# Franzino.net
KiCad netlist of a schematic drawn in EAGLE
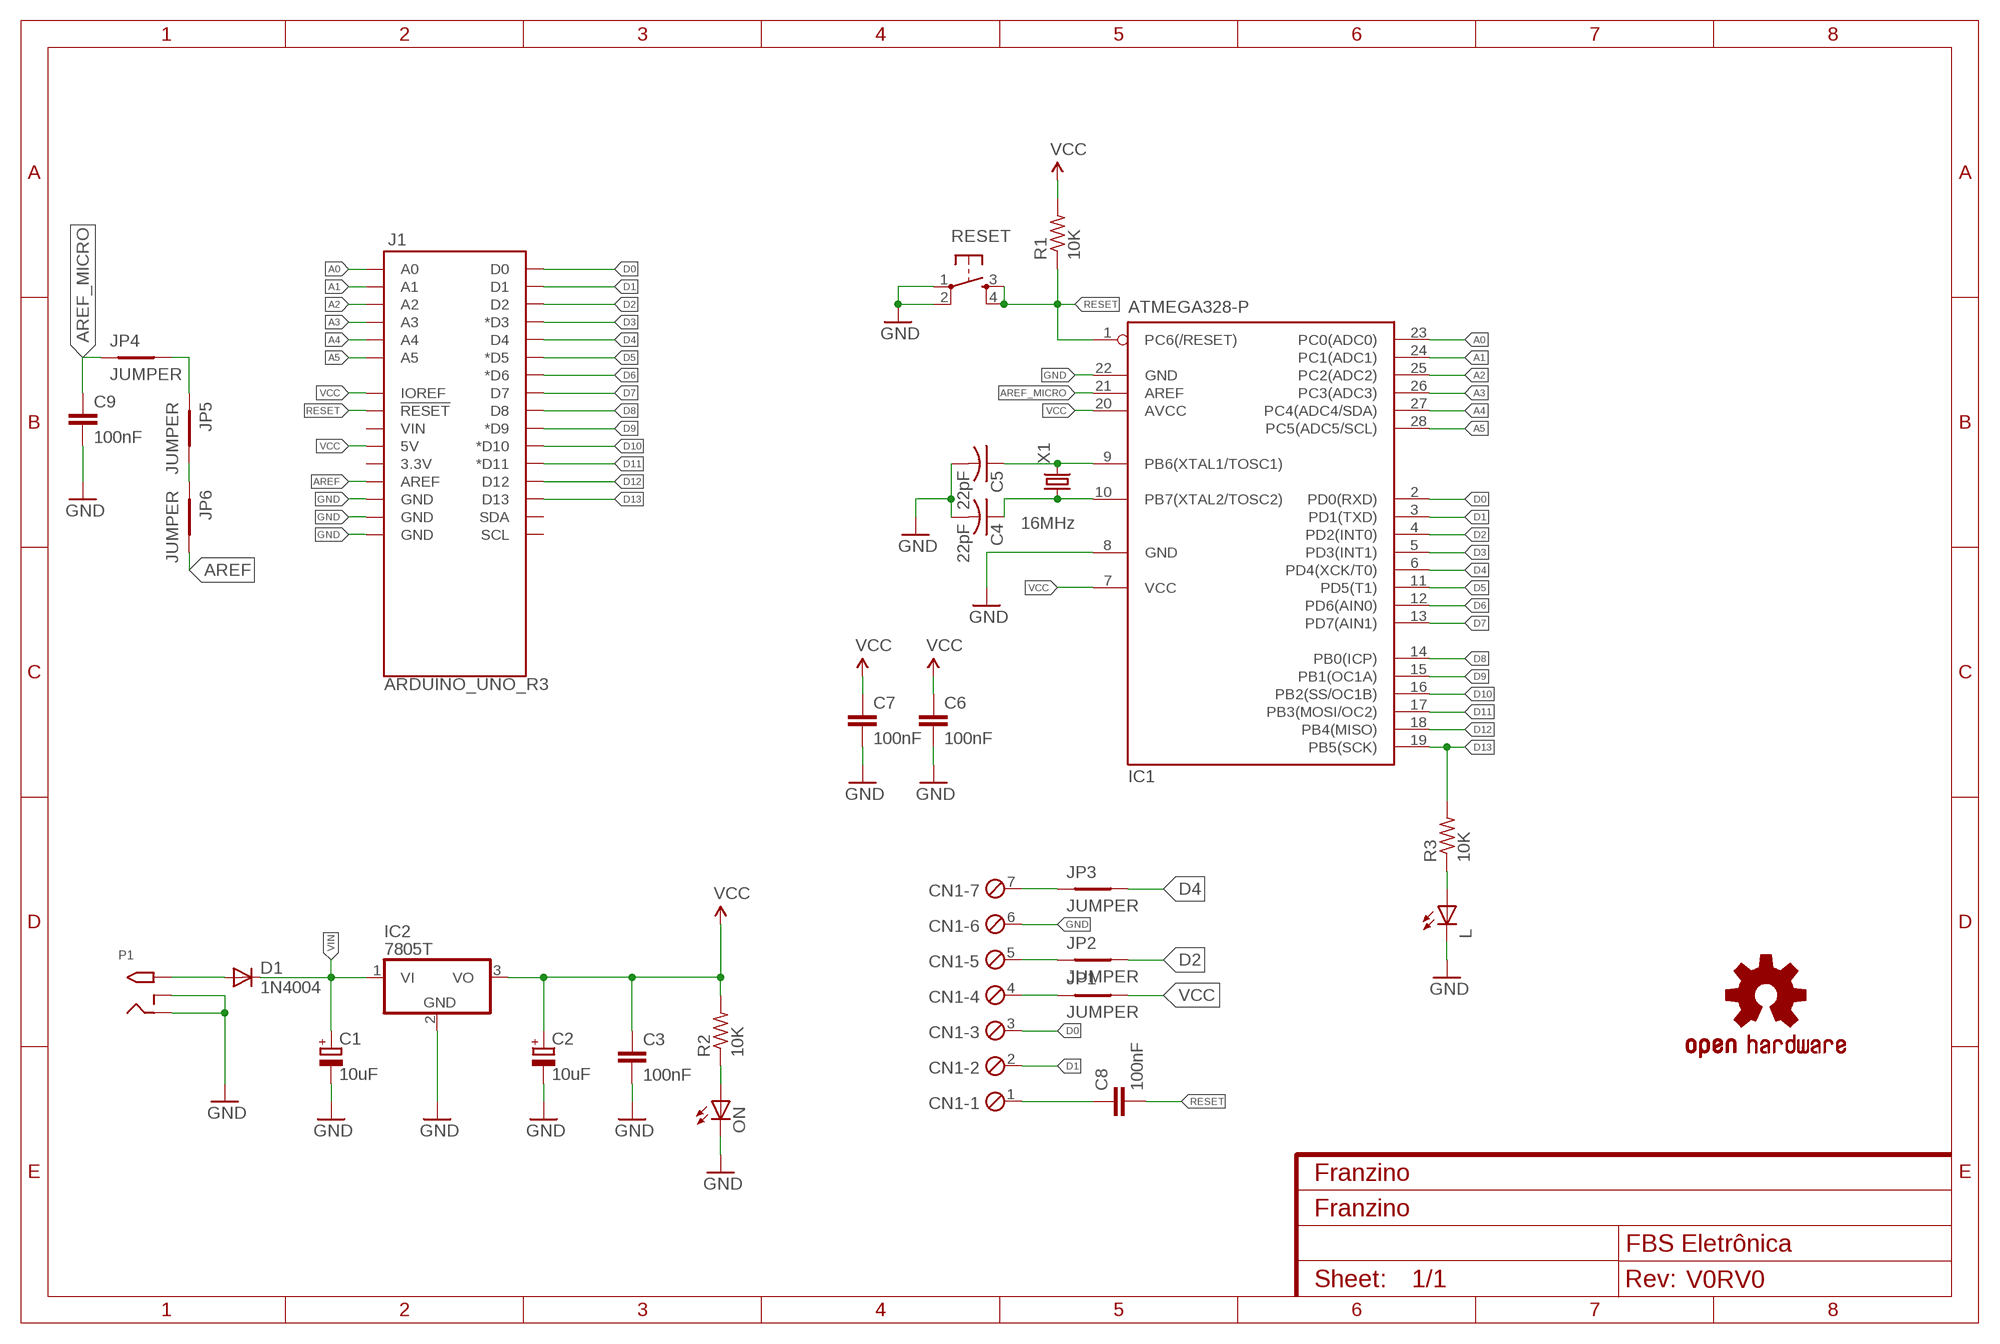
[diagram p0: schematic, sheet 1]

(export (version "E")
  (design (tool "Eeschema 10.0.6"))
  (components
    (comp (ref "C1")
      (value "10uF")
      (footprint "eagle-import:E2,5-6")
      (libsource (lib "eagle-import") (part "CPOL-EUE2.5-6"))
    )
    (comp (ref "C2")
      (value "10uF")
      (footprint "eagle-import:E2,5-6")
      (libsource (lib "eagle-import") (part "CPOL-EUE2.5-6"))
    )
    (comp (ref "C3")
      (value "100nF")
      (footprint "eagle-import:C0805K")
      (libsource (lib "eagle-import") (part "C-EUC0805K"))
    )
    (comp (ref "C4")
      (value "22pF")
      (footprint "eagle-import:C025-024X044")
      (libsource (lib "eagle-import") (part "C-US025-024X044"))
    )
    (comp (ref "C5")
      (value "22pF")
      (footprint "eagle-import:C025-024X044")
      (libsource (lib "eagle-import") (part "C-US025-024X044"))
    )
    (comp (ref "C6")
      (value "100nF")
      (footprint "eagle-import:C0805K")
      (libsource (lib "eagle-import") (part "resistor_C-EUC0805K"))
    )
    (comp (ref "C7")
      (value "100nF")
      (footprint "eagle-import:C0805K")
      (libsource (lib "eagle-import") (part "resistor_C-EUC0805K"))
    )
    (comp (ref "C8")
      (value "100nF")
      (footprint "eagle-import:C0805K")
      (libsource (lib "eagle-import") (part "resistor_C-EUC0805K"))
    )
    (comp (ref "C9")
      (value "100nF")
      (footprint "eagle-import:C0805K")
      (libsource (lib "eagle-import") (part "resistor_C-EUC0805K"))
    )
    (comp (ref "CN1")
      (value "BARRA de PINOS 6 VIAS")
      (footprint "eagle-import:7POL254")
      (libsource (lib "eagle-import") (part "MPT7"))
    )
    (comp (ref "D1")
      (value "1N4004")
      (footprint "eagle-import:DO41-10")
      (libsource (lib "eagle-import") (part "1N4004"))
    )
    (comp (ref "IC1")
      (value "ATMEGA328-P")
      (footprint "eagle-import:DIL28-3")
      (libsource (lib "eagle-import") (part "MEGA8-P"))
    )
    (comp (ref "IC2")
      (value "7805T")
      (footprint "eagle-import:TO220H")
      (libsource (lib "eagle-import") (part "78T05"))
    )
    (comp (ref "J1")
      (value "ARDUINO_UNO_R3")
      (footprint "eagle-import:ARDUINO_UNO_R3_PINS")
      (libsource (lib "eagle-import") (part "ARDUINO_UNO_R3"))
    )
    (comp (ref "JP1")
      (value "JUMPER")
      (footprint "eagle-import:JUMP10")
      (libsource (lib "eagle-import") (part "JUMPER"))
    )
    (comp (ref "JP2")
      (value "JUMPER")
      (footprint "eagle-import:JUMP10")
      (libsource (lib "eagle-import") (part "JUMPER"))
    )
    (comp (ref "JP3")
      (value "JUMPER")
      (footprint "eagle-import:JUMP10")
      (libsource (lib "eagle-import") (part "JUMPER"))
    )
    (comp (ref "JP4")
      (value "JUMPER")
      (footprint "eagle-import:JUMP10")
      (libsource (lib "eagle-import") (part "JUMPER"))
    )
    (comp (ref "JP5")
      (value "JUMPER")
      (footprint "eagle-import:JUMP10")
      (libsource (lib "eagle-import") (part "JUMPER"))
    )
    (comp (ref "JP6")
      (value "JUMPER")
      (footprint "eagle-import:JUMP10")
      (libsource (lib "eagle-import") (part "JUMPER"))
    )
    (comp (ref "L")
      (value "LED 3mm Amarelo")
      (footprint "eagle-import:LED3MM")
      (libsource (lib "eagle-import") (part "LED3MM"))
    )
    (comp (ref "LOGO2")
      (value "OSHW-LOGOL")
      (footprint "eagle-import:OSHW-LOGO-L")
      (libsource (lib "eagle-import") (part "OSHW-LOGOL"))
    )
    (comp (ref "ON")
      (value "LED 3 mm VERDE")
      (footprint "eagle-import:LED3MM")
      (libsource (lib "eagle-import") (part "LED3MM"))
    )
    (comp (ref "P1")
      (value "2.1MMJACKTHM")
      (footprint "eagle-import:PJ-102A")
      (libsource (lib "eagle-import") (part "2.1MMJACKTHM"))
    )
    (comp (ref "R1")
      (value "10K")
      (footprint "eagle-import:0207_10")
      (libsource (lib "eagle-import") (part "R-US_0207/10"))
    )
    (comp (ref "R2")
      (value "10K")
      (footprint "eagle-import:0207_10")
      (libsource (lib "eagle-import") (part "R-US_0207/10"))
    )
    (comp (ref "R3")
      (value "10K")
      (footprint "eagle-import:0207_10")
      (libsource (lib "eagle-import") (part "R-US_0207/10"))
    )
    (comp (ref "RESET")
      (value "CHAVE TACTIL 6 mm")
      (footprint "eagle-import:TACTILE-PTH")
      (libsource (lib "eagle-import") (part "TAC_SWITCHPTH"))
    )
    (comp (ref "X1")
      (value "16MHz")
      (footprint "eagle-import:HC49_S")
      (libsource (lib "eagle-import") (part "CRYSTALHC49S"))
    )
  )
  (nets
    (net (code "1") (name "A0") (class "Default")
      (node (ref "IC1") (pin "23") (pinfunction "PC0(ADC0)_23") (pintype "bidirectional"))
      (node (ref "J1") (pin "A0") (pinfunction "A0_A0") (pintype "bidirectional"))
    )
    (net (code "2") (name "A1") (class "Default")
      (node (ref "IC1") (pin "24") (pinfunction "PC1(ADC1)_24") (pintype "bidirectional"))
      (node (ref "J1") (pin "A1") (pinfunction "A1_A1") (pintype "bidirectional"))
    )
    (net (code "3") (name "A2") (class "Default")
      (node (ref "IC1") (pin "25") (pinfunction "PC2(ADC2)_25") (pintype "bidirectional"))
      (node (ref "J1") (pin "A2") (pinfunction "A2_A2") (pintype "bidirectional"))
    )
    (net (code "4") (name "A3") (class "Default")
      (node (ref "IC1") (pin "26") (pinfunction "PC3(ADC3)_26") (pintype "bidirectional"))
      (node (ref "J1") (pin "A3") (pinfunction "A3_A3") (pintype "bidirectional"))
    )
    (net (code "5") (name "A4") (class "Default")
      (node (ref "IC1") (pin "27") (pinfunction "PC4(ADC4/SDA)_27") (pintype "bidirectional"))
      (node (ref "J1") (pin "A4") (pinfunction "A4_A4") (pintype "bidirectional"))
    )
    (net (code "6") (name "A5") (class "Default")
      (node (ref "IC1") (pin "28") (pinfunction "PC5(ADC5/SCL)_28") (pintype "bidirectional"))
      (node (ref "J1") (pin "A5") (pinfunction "A5_A5") (pintype "bidirectional"))
    )
    (net (code "7") (name "AREF") (class "Default")
      (node (ref "J1") (pin "AREF") (pinfunction "AREF_AREF") (pintype "bidirectional"))
      (node (ref "JP6") (pin "2") (pinfunction "2_2") (pintype "passive"))
    )
    (net (code "8") (name "AREF_MICRO") (class "Default")
      (node (ref "C9") (pin "1") (pinfunction "1_1") (pintype "passive"))
      (node (ref "IC1") (pin "21") (pinfunction "AREF_21") (pintype "passive"))
      (node (ref "JP4") (pin "1") (pinfunction "1_1") (pintype "passive"))
    )
    (net (code "9") (name "D0") (class "Default")
      (node (ref "CN1") (pin "3") (pinfunction "1_3") (pintype "passive"))
      (node (ref "IC1") (pin "2") (pinfunction "PD0(RXD)_2") (pintype "bidirectional"))
      (node (ref "J1") (pin "D0") (pinfunction "D0_D0") (pintype "bidirectional"))
    )
    (net (code "10") (name "D1") (class "Default")
      (node (ref "CN1") (pin "2") (pinfunction "1_2") (pintype "passive"))
      (node (ref "IC1") (pin "3") (pinfunction "PD1(TXD)_3") (pintype "bidirectional"))
      (node (ref "J1") (pin "D1") (pinfunction "D1_D1") (pintype "bidirectional"))
    )
    (net (code "11") (name "D2") (class "Default")
      (node (ref "IC1") (pin "4") (pinfunction "PD2(INT0)_4") (pintype "bidirectional"))
      (node (ref "J1") (pin "D2") (pinfunction "D2_D2") (pintype "bidirectional"))
      (node (ref "JP2") (pin "2") (pinfunction "2_2") (pintype "passive"))
    )
    (net (code "12") (name "D3") (class "Default")
      (node (ref "IC1") (pin "5") (pinfunction "PD3(INT1)_5") (pintype "bidirectional"))
      (node (ref "J1") (pin "D3") (pinfunction "*D3_D3") (pintype "bidirectional"))
    )
    (net (code "13") (name "D4") (class "Default")
      (node (ref "IC1") (pin "6") (pinfunction "PD4(XCK/T0)_6") (pintype "bidirectional"))
      (node (ref "J1") (pin "D4") (pinfunction "D4_D4") (pintype "bidirectional"))
      (node (ref "JP3") (pin "2") (pinfunction "2_2") (pintype "passive"))
    )
    (net (code "14") (name "D5") (class "Default")
      (node (ref "IC1") (pin "11") (pinfunction "PD5(T1)_11") (pintype "bidirectional"))
      (node (ref "J1") (pin "D5") (pinfunction "*D5_D5") (pintype "bidirectional"))
    )
    (net (code "15") (name "D6") (class "Default")
      (node (ref "IC1") (pin "12") (pinfunction "PD6(AIN0)_12") (pintype "bidirectional"))
      (node (ref "J1") (pin "D6") (pinfunction "*D6_D6") (pintype "bidirectional"))
    )
    (net (code "16") (name "D7") (class "Default")
      (node (ref "IC1") (pin "13") (pinfunction "PD7(AIN1)_13") (pintype "bidirectional"))
      (node (ref "J1") (pin "D7") (pinfunction "D7_D7") (pintype "bidirectional"))
    )
    (net (code "17") (name "D8") (class "Default")
      (node (ref "IC1") (pin "14") (pinfunction "PB0(ICP)_14") (pintype "bidirectional"))
      (node (ref "J1") (pin "D8") (pinfunction "D8_D8") (pintype "bidirectional"))
    )
    (net (code "18") (name "D9") (class "Default")
      (node (ref "IC1") (pin "15") (pinfunction "PB1(OC1A)_15") (pintype "bidirectional"))
      (node (ref "J1") (pin "D9") (pinfunction "*D9_D9") (pintype "bidirectional"))
    )
    (net (code "19") (name "D10") (class "Default")
      (node (ref "IC1") (pin "16") (pinfunction "PB2(SS/OC1B)_16") (pintype "bidirectional"))
      (node (ref "J1") (pin "D10") (pinfunction "*D10_D10") (pintype "bidirectional"))
    )
    (net (code "20") (name "D11") (class "Default")
      (node (ref "IC1") (pin "17") (pinfunction "PB3(MOSI/OC2)_17") (pintype "bidirectional"))
      (node (ref "J1") (pin "D11") (pinfunction "*D11_D11") (pintype "bidirectional"))
    )
    (net (code "21") (name "D12") (class "Default")
      (node (ref "IC1") (pin "18") (pinfunction "PB4(MISO)_18") (pintype "bidirectional"))
      (node (ref "J1") (pin "D12") (pinfunction "D12_D12") (pintype "bidirectional"))
    )
    (net (code "22") (name "D13") (class "Default")
      (node (ref "IC1") (pin "19") (pinfunction "PB5(SCK)_19") (pintype "bidirectional"))
      (node (ref "J1") (pin "D13") (pinfunction "D13_D13") (pintype "bidirectional"))
      (node (ref "R3") (pin "2") (pinfunction "2_2") (pintype "passive"))
    )
    (net (code "23") (name "GND") (class "Default")
      (node (ref "C1") (pin "-") (pinfunction "-_-") (pintype "passive"))
      (node (ref "C2") (pin "-") (pinfunction "-_-") (pintype "passive"))
      (node (ref "C3") (pin "2") (pinfunction "2_2") (pintype "passive"))
      (node (ref "C4") (pin "2") (pinfunction "2_2") (pintype "passive"))
      (node (ref "C5") (pin "2") (pinfunction "2_2") (pintype "passive"))
      (node (ref "C6") (pin "2") (pinfunction "2_2") (pintype "passive"))
      (node (ref "C7") (pin "2") (pinfunction "2_2") (pintype "passive"))
      (node (ref "C9") (pin "2") (pinfunction "2_2") (pintype "passive"))
      (node (ref "CN1") (pin "6") (pinfunction "1_6") (pintype "passive"))
      (node (ref "IC1") (pin "22") (pinfunction "GND_22") (pintype "power_in"))
      (node (ref "IC1") (pin "8") (pinfunction "GND_8") (pintype "power_in"))
      (node (ref "IC2") (pin "2") (pinfunction "GND_2") (pintype "passive"))
      (node (ref "J1") (pin "GND@1") (pinfunction "GND_GND@1") (pintype "bidirectional"))
      (node (ref "J1") (pin "GND@2") (pinfunction "GND_GND@2") (pintype "bidirectional"))
      (node (ref "J1") (pin "GND@3") (pinfunction "GND_GND@3") (pintype "bidirectional"))
      (node (ref "L") (pin "K") (pinfunction "C_K") (pintype "passive"))
      (node (ref "ON") (pin "K") (pinfunction "C_K") (pintype "passive"))
      (node (ref "P1") (pin "RING") (pinfunction "RING_RING") (pintype "bidirectional"))
      (node (ref "P1") (pin "RING_SW") (pinfunction "RING_SW_RING_SW") (pintype "bidirectional"))
      (node (ref "RESET") (pin "1") (pinfunction "1_1") (pintype "passive"))
      (node (ref "RESET") (pin "2") (pinfunction "2_2") (pintype "passive"))
    )
    (net (code "24") (name "Net-(C8-Pad1)") (class "Default")
      (node (ref "C8") (pin "1") (pinfunction "1_1") (pintype "passive"))
      (node (ref "CN1") (pin "1") (pinfunction "1_1") (pintype "passive"))
    )
    (net (code "25") (name "Net-(CN1D-1)") (class "Default")
      (node (ref "CN1") (pin "4") (pinfunction "1_4") (pintype "passive"))
      (node (ref "JP1") (pin "1") (pinfunction "1_1") (pintype "passive"))
    )
    (net (code "26") (name "Net-(CN1E-1)") (class "Default")
      (node (ref "CN1") (pin "5") (pinfunction "1_5") (pintype "passive"))
      (node (ref "JP2") (pin "1") (pinfunction "1_1") (pintype "passive"))
    )
    (net (code "27") (name "Net-(CN1G-1)") (class "Default")
      (node (ref "CN1") (pin "7") (pinfunction "1_7") (pintype "passive"))
      (node (ref "JP3") (pin "1") (pinfunction "1_1") (pintype "passive"))
    )
    (net (code "28") (name "Net-(D1-PadA)") (class "Default")
      (node (ref "D1") (pin "A") (pinfunction "A_A") (pintype "passive"))
      (node (ref "P1") (pin "TIP") (pinfunction "TIP_TIP") (pintype "bidirectional"))
    )
    (net (code "29") (name "Net-(IC1-PB6(XTAL1{slash}TOSC1))") (class "Default")
      (node (ref "C5") (pin "1") (pinfunction "1_1") (pintype "passive"))
      (node (ref "IC1") (pin "9") (pinfunction "PB6(XTAL1/TOSC1)_9") (pintype "bidirectional"))
      (node (ref "X1") (pin "2") (pinfunction "2_2") (pintype "passive"))
    )
    (net (code "30") (name "Net-(IC1-PB7(XTAL2{slash}TOSC2))") (class "Default")
      (node (ref "C4") (pin "1") (pinfunction "1_1") (pintype "passive"))
      (node (ref "IC1") (pin "10") (pinfunction "PB7(XTAL2/TOSC2)_10") (pintype "bidirectional"))
      (node (ref "X1") (pin "1") (pinfunction "1_1") (pintype "passive"))
    )
    (net (code "31") (name "Net-(JP4-Pad2)") (class "Default")
      (node (ref "JP4") (pin "2") (pinfunction "2_2") (pintype "passive"))
      (node (ref "JP5") (pin "1") (pinfunction "1_1") (pintype "passive"))
    )
    (net (code "32") (name "Net-(JP5-Pad2)") (class "Default")
      (node (ref "JP5") (pin "2") (pinfunction "2_2") (pintype "passive"))
      (node (ref "JP6") (pin "1") (pinfunction "1_1") (pintype "passive"))
    )
    (net (code "33") (name "Net-(L-PadA)") (class "Default")
      (node (ref "L") (pin "A") (pinfunction "A_A") (pintype "passive"))
      (node (ref "R3") (pin "1") (pinfunction "1_1") (pintype "passive"))
    )
    (net (code "34") (name "Net-(ON-PadA)") (class "Default")
      (node (ref "ON") (pin "A") (pinfunction "A_A") (pintype "passive"))
      (node (ref "R2") (pin "1") (pinfunction "1_1") (pintype "passive"))
    )
    (net (code "35") (name "RESET") (class "Default")
      (node (ref "C8") (pin "2") (pinfunction "2_2") (pintype "passive"))
      (node (ref "IC1") (pin "1") (pinfunction "PC6(/RESET)_1") (pintype "bidirectional"))
      (node (ref "J1") (pin "RESET@1") (pinfunction "~{RESET}_RESET@1") (pintype "bidirectional"))
      (node (ref "R1") (pin "1") (pinfunction "1_1") (pintype "passive"))
      (node (ref "RESET") (pin "3") (pinfunction "3_3") (pintype "passive"))
      (node (ref "RESET") (pin "4") (pinfunction "4_4") (pintype "passive"))
    )
    (net (code "36") (name "VCC") (class "Default")
      (node (ref "C2") (pin "+") (pinfunction "+_+") (pintype "passive"))
      (node (ref "C3") (pin "1") (pinfunction "1_1") (pintype "passive"))
      (node (ref "C6") (pin "1") (pinfunction "1_1") (pintype "passive"))
      (node (ref "C7") (pin "1") (pinfunction "1_1") (pintype "passive"))
      (node (ref "IC1") (pin "20") (pinfunction "AVCC_20") (pintype "power_in"))
      (node (ref "IC1") (pin "7") (pinfunction "VCC_7") (pintype "power_in"))
      (node (ref "IC2") (pin "3") (pinfunction "VO_3") (pintype "passive"))
      (node (ref "J1") (pin "5V") (pinfunction "5V_5V") (pintype "bidirectional"))
      (node (ref "J1") (pin "IOREF") (pinfunction "IOREF_IOREF") (pintype "bidirectional"))
      (node (ref "JP1") (pin "2") (pinfunction "2_2") (pintype "passive"))
      (node (ref "R1") (pin "2") (pinfunction "2_2") (pintype "passive"))
      (node (ref "R2") (pin "2") (pinfunction "2_2") (pintype "passive"))
    )
    (net (code "37") (name "VIN") (class "Default")
      (node (ref "C1") (pin "+") (pinfunction "+_+") (pintype "passive"))
      (node (ref "D1") (pin "C") (pinfunction "C_C") (pintype "passive"))
      (node (ref "IC2") (pin "1") (pinfunction "VI_1") (pintype "input"))
    )
    (net (code "38") (name "unconnected-(J1-Pad3.3V)") (class "Default")
      (node (ref "J1") (pin "3.3V") (pinfunction "3.3V_3.3V") (pintype "bidirectional"))
    )
    (net (code "39") (name "unconnected-(J1-PadSCL)") (class "Default")
      (node (ref "J1") (pin "SCL") (pinfunction "SCL_SCL") (pintype "bidirectional"))
    )
    (net (code "40") (name "unconnected-(J1-PadSDA)") (class "Default")
      (node (ref "J1") (pin "SDA") (pinfunction "SDA_SDA") (pintype "bidirectional"))
    )
    (net (code "41") (name "unconnected-(J1-PadVIN)") (class "Default")
      (node (ref "J1") (pin "VIN") (pinfunction "VIN_VIN") (pintype "bidirectional"))
    )
  )
)
